# 4_RFM95W.net
KiCad netlist of a schematic drawn in Altium Designer
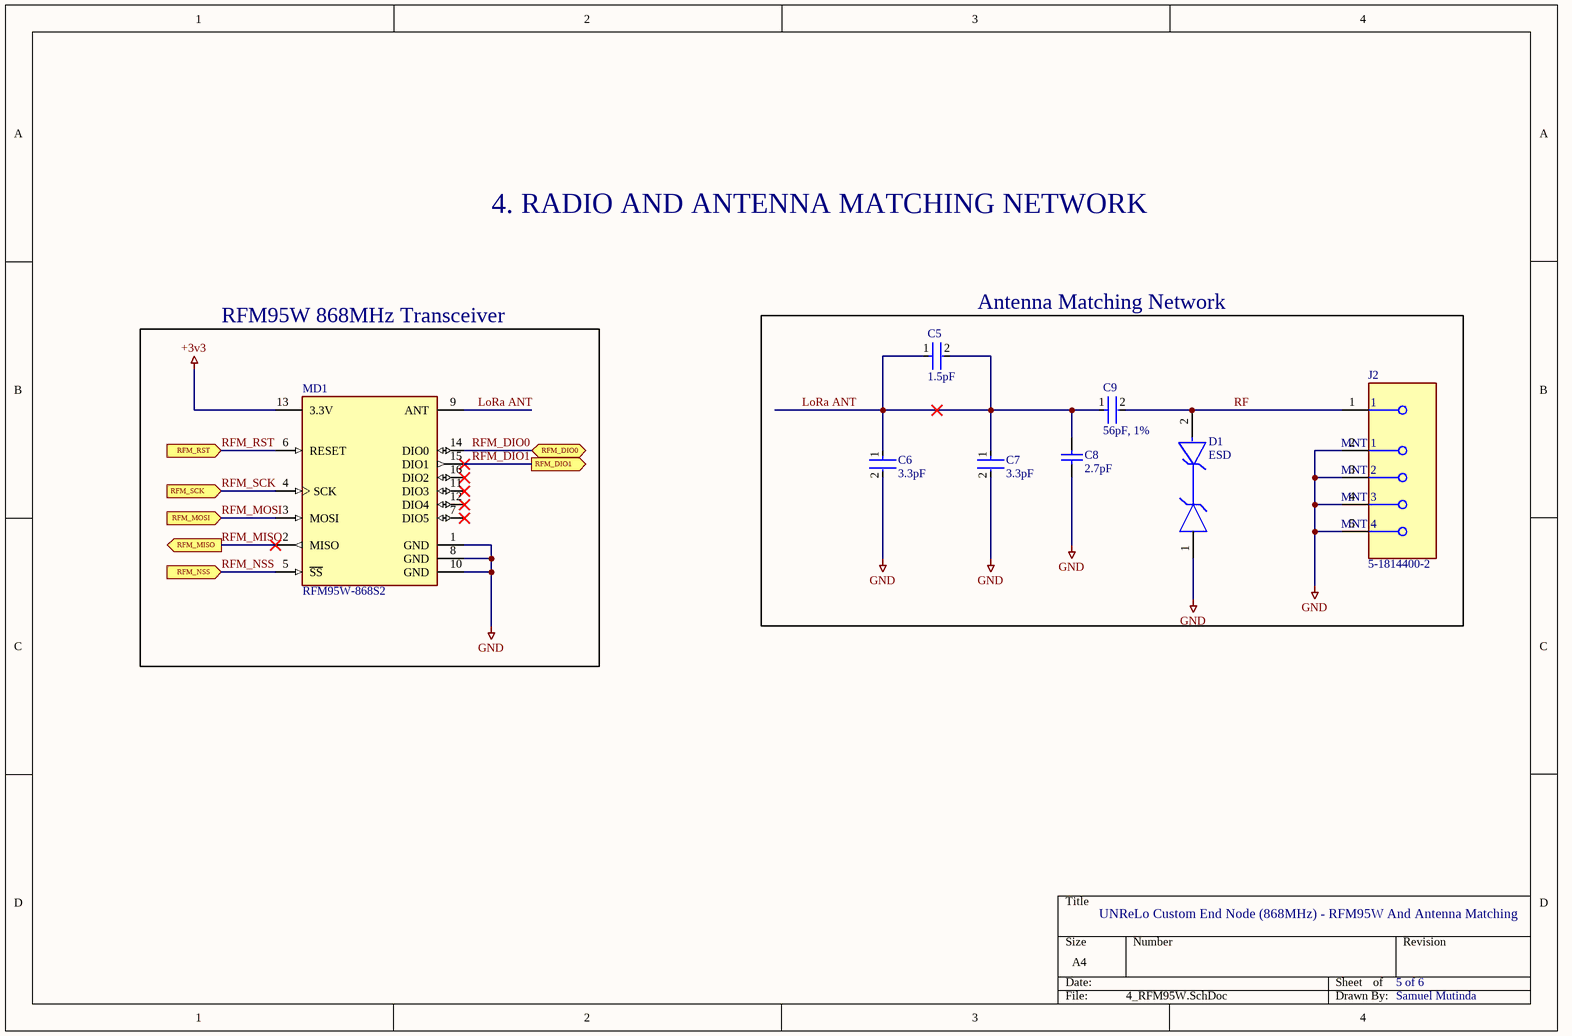
[diagram p0: 4_RFM95W.SchDoc]

(export (version "E")
  (design (tool "Eeschema 10.0.6"))
  (components
    (comp (ref "C5")
      (value "1.5pF")
      (footprint "FP-GJM155-0_05-IPC_C")
      (description "Multi-Layer Ceramic Capacitor 1.5pF C0G  ±0.1pF 0402 Paper T/R")
      (fields (field (name "VOLTAGE") "50V"))
      (libsource (lib "Altium Content Vault") (part "02cd4be3c70576c341d710602a673aa"))
    )
    (comp (ref "C6")
      (value "3.3pF")
      (footprint "FP-C0603C-CF-MFG")
      (description "CAP CER 3.3PF 50V NP0 0603")
      (fields
        (field (name "TOLERANCE") "0.25 pF")
        (field (name "OCTOPART") "https://octopart.com/c0603c339c5gactu-kemet-3701205")
      )
      (libsource (lib "Altium Content Vault") (part "b4654b650e69147ec39a6b967a45e02"))
    )
    (comp (ref "C7")
      (value "3.3pF")
      (footprint "FP-C0603C-CF-MFG")
      (description "CAP CER 3.3PF 50V NP0 0603")
      (fields
        (field (name "TOLERANCE") "0.25 pF")
        (field (name "OCTOPART") "https://octopart.com/c0603c339c5gactu-kemet-3701205")
      )
      (libsource (lib "Altium Content Vault") (part "b4654b650e69147ec39a6b967a45e02"))
    )
    (comp (ref "C8")
      (value "2.7pF")
      (footprint "CAPC1006X50X20ML10T10")
      (fields (field (name "MANUFACTURER") "AVX Interconnect / Elco"))
      (libsource (lib "Altium Content Vault") (part "CAP"))
    )
    (comp (ref "C9")
      (value "56pF, 1%")
      (footprint "FP-C0603C-CF-MFG")
      (description "CAP CER 56PF 50V 1% NP0 0603")
      (fields
        (field (name "TOLERANCE") "0.01")
        (field (name "OCTOPART") "https://octopart.com/c0603c560f5gactu-kemet-9143760")
      )
      (libsource (lib "Altium Content Vault") (part "b4654b650e69147ec39a6b967a45e02"))
    )
    (comp (ref "D1")
      (value "ESD")
      (footprint "FP-711AM-CA-MFG")
      (description "TVS DIODE 5.3V 2XDFN")
      (fields (field (name "OCTOPART") "https://octopart.com/szesd7471n2t5g-on+semiconductor-47358903"))
      (libsource (lib "Altium Content Vault") (part "0b9db586c93572e573b6553f432f587"))
    )
    (comp (ref "J2")
      (value "5-1814400-2")
      (footprint "FP-5-1814400-2-MFG")
      (description "CONN SMA JACK R/A 50 OHM PCB")
      (libsource (lib "Altium Content Vault") (part "42d0677c2d2b90080c021db52569f63"))
    )
    (comp (ref "MD1")
      (value "RFM95W-868S2")
      (footprint "FP-RFM95W-868S2-MFG")
      (description "RX TXRX MODULE ISM < 1GHZ SMD")
      (libsource (lib "Altium Content Vault") (part "17626aa6fba47fab2b206b7c140802e"))
    )
  )
  (nets
    (net (code "1") (name "+3v3") (class "Default")
      (node (ref "MD1") (pin "13") (pinfunction "3.3V_13") (pintype "power_in"))
    )
    (net (code "2") (name "/LoRa ANT") (class "Default")
      (node (ref "C5") (pin "1") (pinfunction "1_1") (pintype "passive"))
      (node (ref "C5") (pin "2") (pinfunction "2_2") (pintype "passive"))
      (node (ref "C6") (pin "1") (pinfunction "1_1") (pintype "passive"))
      (node (ref "C7") (pin "1") (pinfunction "1_1") (pintype "passive"))
      (node (ref "C8") (pin "2") (pinfunction "2_2") (pintype "passive"))
      (node (ref "C9") (pin "1") (pinfunction "1_1") (pintype "passive"))
      (node (ref "MD1") (pin "9") (pinfunction "ANT_9") (pintype "passive"))
    )
    (net (code "3") (name "/RF") (class "Default")
      (node (ref "C9") (pin "2") (pinfunction "2_2") (pintype "passive"))
      (node (ref "D1") (pin "2") (pinfunction "2_2") (pintype "passive"))
      (node (ref "J2") (pin "1") (pinfunction "1_1") (pintype "passive"))
    )
    (net (code "4") (name "/RFM_DIO0") (class "Default")
      (node (ref "MD1") (pin "14") (pinfunction "DIO0_14") (pintype "bidirectional"))
    )
    (net (code "5") (name "/RFM_DIO1") (class "Default")
      (node (ref "MD1") (pin "15") (pinfunction "DIO1_15") (pintype "output+no_connect"))
    )
    (net (code "6") (name "/RFM_MISO") (class "Default")
      (node (ref "MD1") (pin "2") (pinfunction "MISO_2") (pintype "output+no_connect"))
    )
    (net (code "7") (name "/RFM_MOSI") (class "Default")
      (node (ref "MD1") (pin "3") (pinfunction "MOSI_3") (pintype "input"))
    )
    (net (code "8") (name "/RFM_NSS") (class "Default")
      (node (ref "MD1") (pin "5") (pinfunction "~{SS}_5") (pintype "input"))
    )
    (net (code "9") (name "/RFM_RST") (class "Default")
      (node (ref "MD1") (pin "6") (pinfunction "RESET_6") (pintype "input"))
    )
    (net (code "10") (name "/RFM_SCK") (class "Default")
      (node (ref "MD1") (pin "4") (pinfunction "SCK_4") (pintype "input"))
    )
    (net (code "11") (name "GND") (class "Default")
      (node (ref "C6") (pin "2") (pinfunction "2_2") (pintype "passive"))
      (node (ref "C7") (pin "2") (pinfunction "2_2") (pintype "passive"))
      (node (ref "C8") (pin "1") (pinfunction "1_1") (pintype "passive"))
      (node (ref "D1") (pin "1") (pinfunction "1_1") (pintype "passive"))
      (node (ref "J2") (pin "2") (pinfunction "MNT_1_2") (pintype "passive"))
      (node (ref "J2") (pin "3") (pinfunction "MNT_2_3") (pintype "passive"))
      (node (ref "J2") (pin "4") (pinfunction "MNT_3_4") (pintype "passive"))
      (node (ref "J2") (pin "5") (pinfunction "MNT_4_5") (pintype "passive"))
      (node (ref "MD1") (pin "1") (pinfunction "GND_1") (pintype "power_in"))
      (node (ref "MD1") (pin "10") (pinfunction "GND_10") (pintype "power_in"))
      (node (ref "MD1") (pin "8") (pinfunction "GND_8") (pintype "power_in"))
    )
    (net (code "12") (name "unconnected-(MD1-DIO2-Pad16)") (class "Default")
      (node (ref "MD1") (pin "16") (pinfunction "DIO2_16") (pintype "bidirectional+no_connect"))
    )
    (net (code "13") (name "unconnected-(MD1-DIO3-Pad11)") (class "Default")
      (node (ref "MD1") (pin "11") (pinfunction "DIO3_11") (pintype "bidirectional+no_connect"))
    )
    (net (code "14") (name "unconnected-(MD1-DIO4-Pad12)") (class "Default")
      (node (ref "MD1") (pin "12") (pinfunction "DIO4_12") (pintype "bidirectional+no_connect"))
    )
    (net (code "15") (name "unconnected-(MD1-DIO5-Pad7)") (class "Default")
      (node (ref "MD1") (pin "7") (pinfunction "DIO5_7") (pintype "bidirectional+no_connect"))
    )
  )
)
